# ThermistorCPTSCHEMATIC.net
KiCad netlist of a schematic drawn in EAGLE
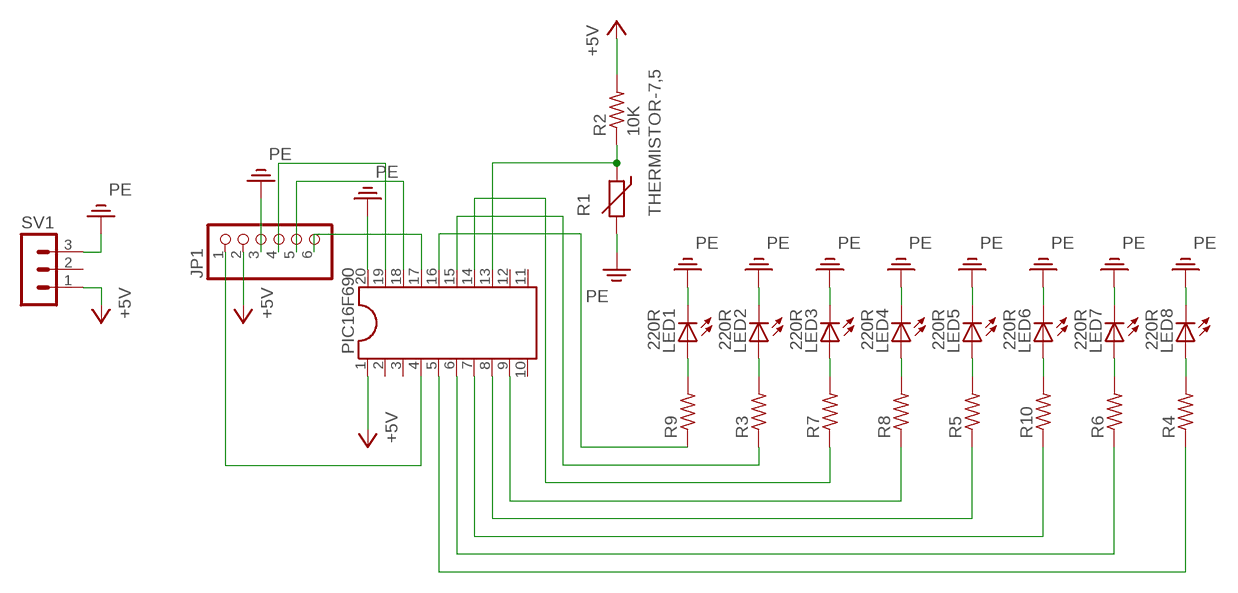
[diagram p0: schematic, sheet 1]

(export (version "E")
  (design (tool "Eeschema 10.0.6"))
  (components
    (comp (ref "JP1")
      (value "PINHD-1X6")
      (footprint "eagle-import:1X06")
      (libsource (lib "eagle-import") (part "PINHD-1X6"))
    )
    (comp (ref "LED1")
      (value "220R")
      (footprint "eagle-import:LED5MM")
      (libsource (lib "eagle-import") (part "LED5MM"))
    )
    (comp (ref "LED2")
      (value "220R")
      (footprint "eagle-import:LED5MM")
      (libsource (lib "eagle-import") (part "LED5MM"))
    )
    (comp (ref "LED3")
      (value "220R")
      (footprint "eagle-import:LED5MM")
      (libsource (lib "eagle-import") (part "LED5MM"))
    )
    (comp (ref "LED4")
      (value "220R")
      (footprint "eagle-import:LED5MM")
      (libsource (lib "eagle-import") (part "LED5MM"))
    )
    (comp (ref "LED5")
      (value "220R")
      (footprint "eagle-import:LED5MM")
      (libsource (lib "eagle-import") (part "LED5MM"))
    )
    (comp (ref "LED6")
      (value "220R")
      (footprint "eagle-import:LED5MM")
      (libsource (lib "eagle-import") (part "LED5MM"))
    )
    (comp (ref "LED7")
      (value "220R")
      (footprint "eagle-import:LED5MM")
      (libsource (lib "eagle-import") (part "LED5MM"))
    )
    (comp (ref "LED8")
      (value "220R")
      (footprint "eagle-import:LED5MM")
      (libsource (lib "eagle-import") (part "LED5MM"))
    )
    (comp (ref "PIC16F690")
      (value "DIL20")
      (footprint "eagle-import:DIL20")
      (libsource (lib "eagle-import") (part "DIL20"))
    )
    (comp (ref "R1")
      (value "THERMISTOR-7,5")
      (footprint "eagle-import:R-7,5")
      (libsource (lib "eagle-import") (part "THERMISTOR-7,5"))
    )
    (comp (ref "R2")
      (value "10K")
      (footprint "eagle-import:0207_10")
      (libsource (lib "eagle-import") (part "R-US_0207/10"))
    )
    (comp (ref "R3")
      (value "R-US_0207/10")
      (footprint "eagle-import:0207_10")
      (libsource (lib "eagle-import") (part "R-US_0207/10"))
    )
    (comp (ref "R4")
      (value "R-US_0207/10")
      (footprint "eagle-import:0207_10")
      (libsource (lib "eagle-import") (part "R-US_0207/10"))
    )
    (comp (ref "R5")
      (value "R-US_0207/10")
      (footprint "eagle-import:0207_10")
      (libsource (lib "eagle-import") (part "R-US_0207/10"))
    )
    (comp (ref "R6")
      (value "R-US_0207/10")
      (footprint "eagle-import:0207_10")
      (libsource (lib "eagle-import") (part "R-US_0207/10"))
    )
    (comp (ref "R7")
      (value "R-US_0207/10")
      (footprint "eagle-import:0207_10")
      (libsource (lib "eagle-import") (part "R-US_0207/10"))
    )
    (comp (ref "R8")
      (value "R-US_0207/10")
      (footprint "eagle-import:0207_10")
      (libsource (lib "eagle-import") (part "R-US_0207/10"))
    )
    (comp (ref "R9")
      (value "R-US_0207/10")
      (footprint "eagle-import:0207_10")
      (libsource (lib "eagle-import") (part "R-US_0207/10"))
    )
    (comp (ref "R10")
      (value "R-US_0207/10")
      (footprint "eagle-import:0207_10")
      (libsource (lib "eagle-import") (part "R-US_0207/10"))
    )
    (comp (ref "SV1")
      (value "MA03-1")
      (footprint "eagle-import:MA03-1")
      (libsource (lib "eagle-import") (part "MA03-1"))
    )
  )
  (nets
    (net (code "1") (name "+5V") (class "Default")
      (node (ref "JP1") (pin "2") (pinfunction "2_2") (pintype "passive"))
      (node (ref "PIC16F690") (pin "1") (pinfunction "1_1") (pintype "passive"))
      (node (ref "R2") (pin "2") (pinfunction "2_2") (pintype "passive"))
      (node (ref "SV1") (pin "1") (pinfunction "1_1") (pintype "passive"))
    )
    (net (code "2") (name "Net-(JP1-Pad1)") (class "Default")
      (node (ref "JP1") (pin "1") (pinfunction "1_1") (pintype "passive"))
      (node (ref "PIC16F690") (pin "4") (pinfunction "4_4") (pintype "passive"))
    )
    (net (code "3") (name "Net-(JP1-Pad4)") (class "Default")
      (node (ref "JP1") (pin "4") (pinfunction "4_4") (pintype "passive"))
      (node (ref "PIC16F690") (pin "19") (pinfunction "19_19") (pintype "passive"))
    )
    (net (code "4") (name "Net-(JP1-Pad5)") (class "Default")
      (node (ref "JP1") (pin "5") (pinfunction "5_5") (pintype "passive"))
      (node (ref "PIC16F690") (pin "18") (pinfunction "18_18") (pintype "passive"))
    )
    (net (code "5") (name "Net-(JP1-Pad6)") (class "Default")
      (node (ref "JP1") (pin "6") (pinfunction "6_6") (pintype "passive"))
      (node (ref "PIC16F690") (pin "17") (pinfunction "17_17") (pintype "passive"))
    )
    (net (code "6") (name "Net-(LED1-PadA)") (class "Default")
      (node (ref "LED1") (pin "A") (pinfunction "A_A") (pintype "passive"))
      (node (ref "R9") (pin "2") (pinfunction "2_2") (pintype "passive"))
    )
    (net (code "7") (name "Net-(LED2-PadA)") (class "Default")
      (node (ref "LED2") (pin "A") (pinfunction "A_A") (pintype "passive"))
      (node (ref "R3") (pin "2") (pinfunction "2_2") (pintype "passive"))
    )
    (net (code "8") (name "Net-(LED3-PadA)") (class "Default")
      (node (ref "LED3") (pin "A") (pinfunction "A_A") (pintype "passive"))
      (node (ref "R7") (pin "2") (pinfunction "2_2") (pintype "passive"))
    )
    (net (code "9") (name "Net-(LED4-PadA)") (class "Default")
      (node (ref "LED4") (pin "A") (pinfunction "A_A") (pintype "passive"))
      (node (ref "R8") (pin "2") (pinfunction "2_2") (pintype "passive"))
    )
    (net (code "10") (name "Net-(LED5-PadA)") (class "Default")
      (node (ref "LED5") (pin "A") (pinfunction "A_A") (pintype "passive"))
      (node (ref "R5") (pin "2") (pinfunction "2_2") (pintype "passive"))
    )
    (net (code "11") (name "Net-(LED6-PadA)") (class "Default")
      (node (ref "LED6") (pin "A") (pinfunction "A_A") (pintype "passive"))
      (node (ref "R10") (pin "2") (pinfunction "2_2") (pintype "passive"))
    )
    (net (code "12") (name "Net-(LED7-PadA)") (class "Default")
      (node (ref "LED7") (pin "A") (pinfunction "A_A") (pintype "passive"))
      (node (ref "R6") (pin "2") (pinfunction "2_2") (pintype "passive"))
    )
    (net (code "13") (name "Net-(LED8-PadA)") (class "Default")
      (node (ref "LED8") (pin "A") (pinfunction "A_A") (pintype "passive"))
      (node (ref "R4") (pin "2") (pinfunction "2_2") (pintype "passive"))
    )
    (net (code "14") (name "Net-(PIC16F690-Pad5)") (class "Default")
      (node (ref "PIC16F690") (pin "5") (pinfunction "5_5") (pintype "passive"))
      (node (ref "R4") (pin "1") (pinfunction "1_1") (pintype "passive"))
    )
    (net (code "15") (name "Net-(PIC16F690-Pad6)") (class "Default")
      (node (ref "PIC16F690") (pin "6") (pinfunction "6_6") (pintype "passive"))
      (node (ref "R6") (pin "1") (pinfunction "1_1") (pintype "passive"))
    )
    (net (code "16") (name "Net-(PIC16F690-Pad7)") (class "Default")
      (node (ref "PIC16F690") (pin "7") (pinfunction "7_7") (pintype "passive"))
      (node (ref "R10") (pin "1") (pinfunction "1_1") (pintype "passive"))
    )
    (net (code "17") (name "Net-(PIC16F690-Pad8)") (class "Default")
      (node (ref "PIC16F690") (pin "8") (pinfunction "8_8") (pintype "passive"))
      (node (ref "R5") (pin "1") (pinfunction "1_1") (pintype "passive"))
    )
    (net (code "18") (name "Net-(PIC16F690-Pad9)") (class "Default")
      (node (ref "PIC16F690") (pin "9") (pinfunction "9_9") (pintype "passive"))
      (node (ref "R8") (pin "1") (pinfunction "1_1") (pintype "passive"))
    )
    (net (code "19") (name "Net-(PIC16F690-Pad13)") (class "Default")
      (node (ref "PIC16F690") (pin "13") (pinfunction "13_13") (pintype "passive"))
      (node (ref "R1") (pin "1") (pinfunction "1_1") (pintype "passive"))
      (node (ref "R2") (pin "1") (pinfunction "1_1") (pintype "passive"))
    )
    (net (code "20") (name "Net-(PIC16F690-Pad14)") (class "Default")
      (node (ref "PIC16F690") (pin "14") (pinfunction "14_14") (pintype "passive"))
      (node (ref "R7") (pin "1") (pinfunction "1_1") (pintype "passive"))
    )
    (net (code "21") (name "Net-(PIC16F690-Pad15)") (class "Default")
      (node (ref "PIC16F690") (pin "15") (pinfunction "15_15") (pintype "passive"))
      (node (ref "R3") (pin "1") (pinfunction "1_1") (pintype "passive"))
    )
    (net (code "22") (name "Net-(PIC16F690-Pad16)") (class "Default")
      (node (ref "PIC16F690") (pin "16") (pinfunction "16_16") (pintype "passive"))
      (node (ref "R9") (pin "1") (pinfunction "1_1") (pintype "passive"))
    )
    (net (code "23") (name "PE") (class "Default")
      (node (ref "JP1") (pin "3") (pinfunction "3_3") (pintype "passive"))
      (node (ref "LED1") (pin "K") (pinfunction "C_K") (pintype "passive"))
      (node (ref "LED2") (pin "K") (pinfunction "C_K") (pintype "passive"))
      (node (ref "LED3") (pin "K") (pinfunction "C_K") (pintype "passive"))
      (node (ref "LED4") (pin "K") (pinfunction "C_K") (pintype "passive"))
      (node (ref "LED5") (pin "K") (pinfunction "C_K") (pintype "passive"))
      (node (ref "LED6") (pin "K") (pinfunction "C_K") (pintype "passive"))
      (node (ref "LED7") (pin "K") (pinfunction "C_K") (pintype "passive"))
      (node (ref "LED8") (pin "K") (pinfunction "C_K") (pintype "passive"))
      (node (ref "PIC16F690") (pin "20") (pinfunction "20_20") (pintype "passive"))
      (node (ref "R1") (pin "2") (pinfunction "2_2") (pintype "passive"))
      (node (ref "SV1") (pin "3") (pinfunction "3_3") (pintype "passive"))
    )
    (net (code "24") (name "unconnected-(PIC16F690-Pad2)") (class "Default")
      (node (ref "PIC16F690") (pin "2") (pinfunction "2_2") (pintype "passive"))
    )
    (net (code "25") (name "unconnected-(PIC16F690-Pad3)") (class "Default")
      (node (ref "PIC16F690") (pin "3") (pinfunction "3_3") (pintype "passive"))
    )
    (net (code "26") (name "unconnected-(PIC16F690-Pad10)") (class "Default")
      (node (ref "PIC16F690") (pin "10") (pinfunction "10_10") (pintype "passive"))
    )
    (net (code "27") (name "unconnected-(PIC16F690-Pad11)") (class "Default")
      (node (ref "PIC16F690") (pin "11") (pinfunction "11_11") (pintype "passive"))
    )
    (net (code "28") (name "unconnected-(PIC16F690-Pad12)") (class "Default")
      (node (ref "PIC16F690") (pin "12") (pinfunction "12_12") (pintype "passive"))
    )
    (net (code "29") (name "unconnected-(SV1-Pad2)") (class "Default")
      (node (ref "SV1") (pin "2") (pinfunction "2_2") (pintype "passive"))
    )
  )
)
